# ONOFRE_WIRE_SHIELD.net
KiCad netlist of a schematic drawn in EAGLE
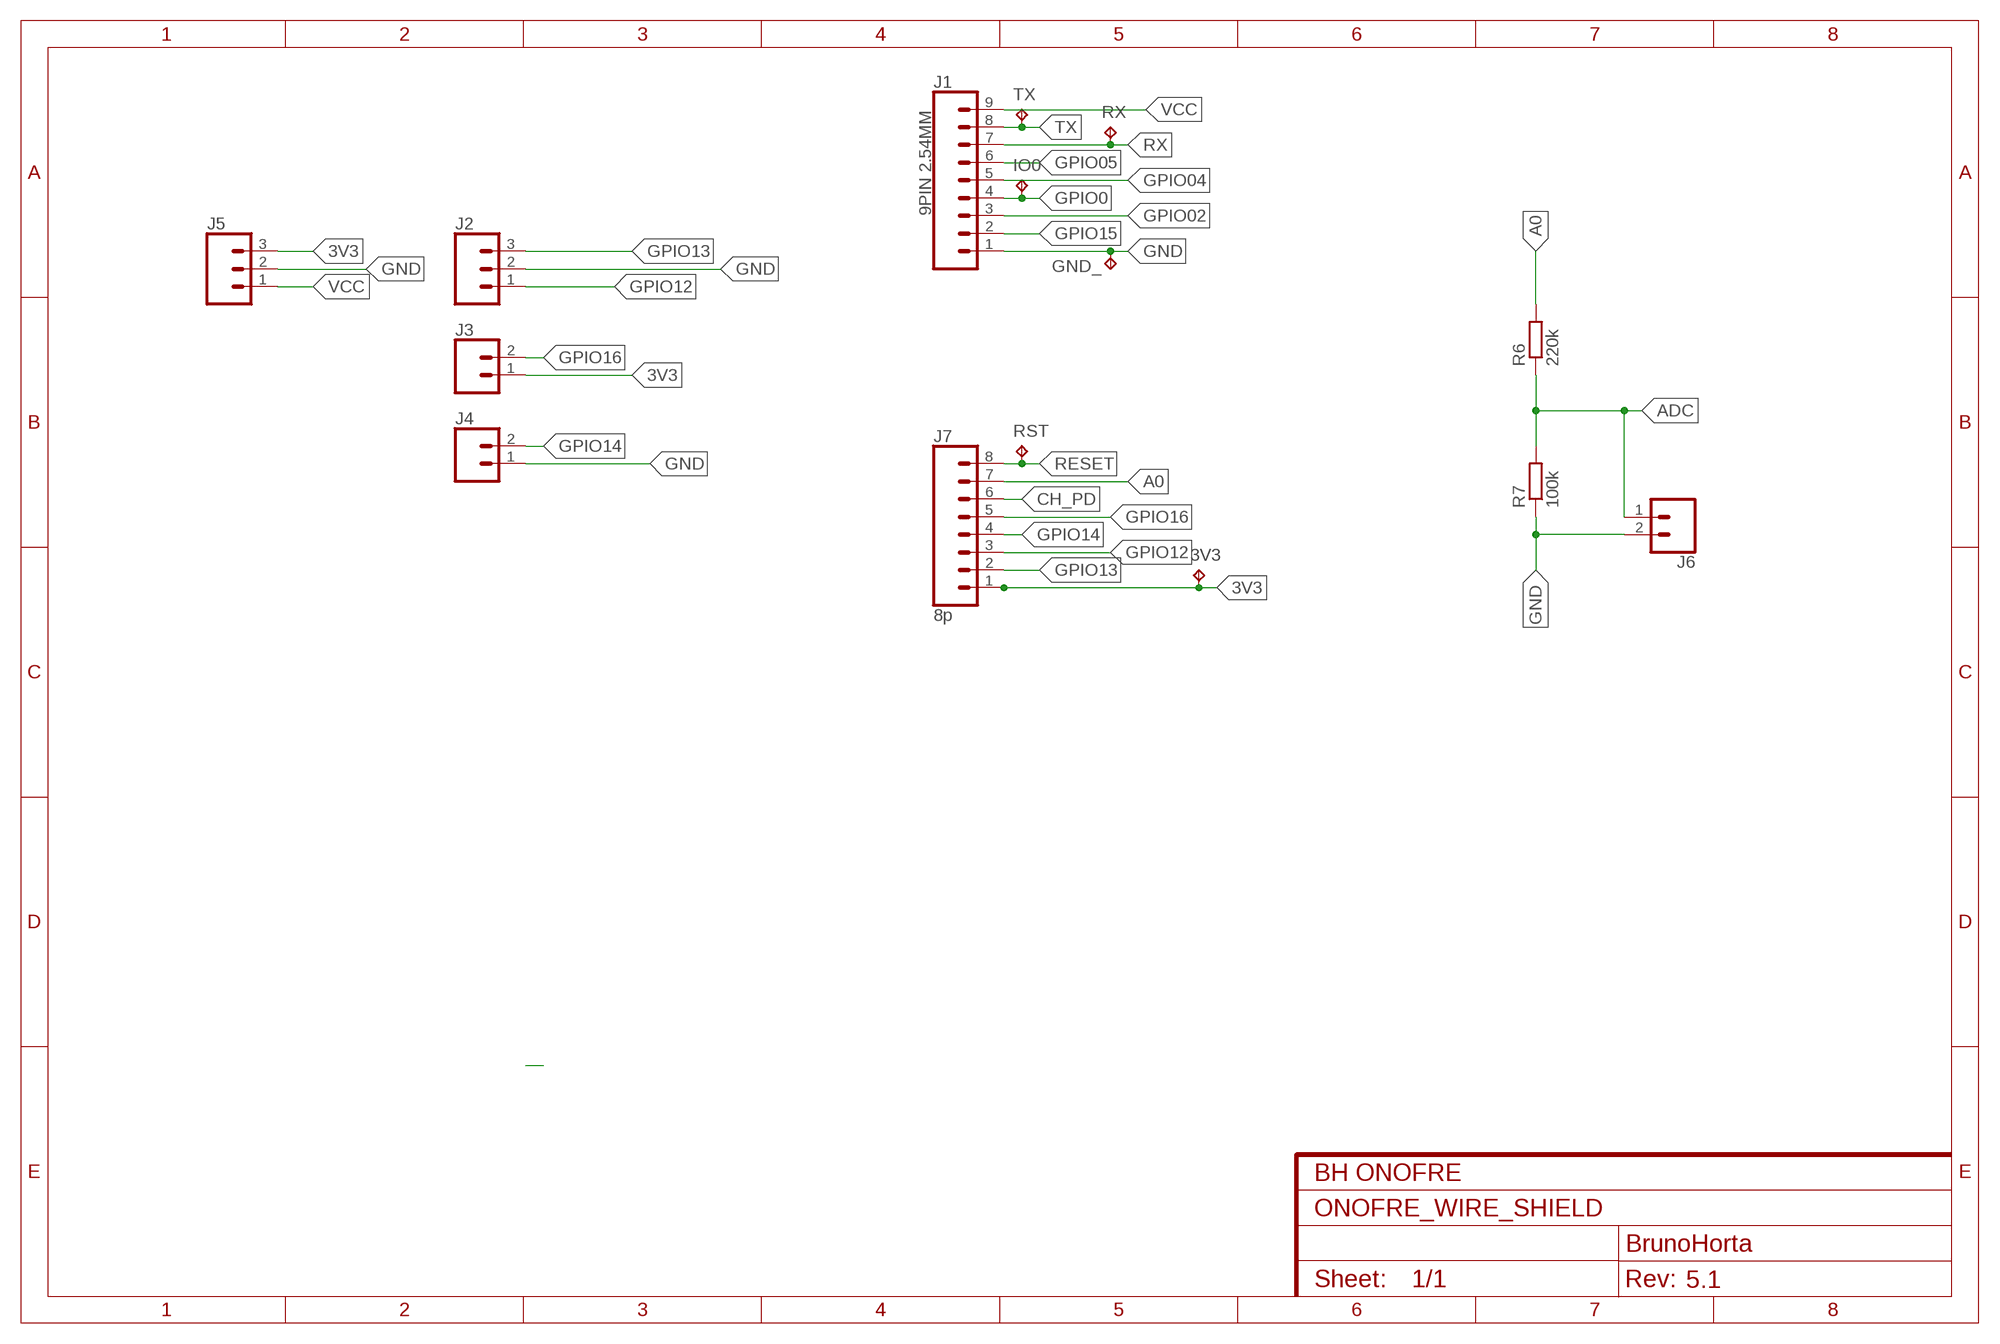
[diagram p0: schematic, sheet 1]

(export (version "E")
  (design (tool "Eeschema 10.0.6"))
  (components
    (comp (ref "3V3")
      (value "TPB1,27")
      (footprint "eagle-import:B1,27")
      (libsource (lib "eagle-import") (part "TPB1,27"))
    )
    (comp (ref "GND_")
      (value "TPB1,27")
      (footprint "eagle-import:B1,27")
      (libsource (lib "eagle-import") (part "TPB1,27"))
    )
    (comp (ref "IO0")
      (value "TPB1,27")
      (footprint "eagle-import:B1,27")
      (libsource (lib "eagle-import") (part "TPB1,27"))
    )
    (comp (ref "J1")
      (value "9PIN 2.54MM")
      (footprint "eagle-import:1X09")
      (libsource (lib "eagle-import") (part "CONN_09"))
    )
    (comp (ref "J2")
      (value "CONN_03")
      (footprint "eagle-import:1X03")
      (libsource (lib "eagle-import") (part "CONN_03"))
    )
    (comp (ref "J3")
      (value "CONN_02")
      (footprint "eagle-import:1X02")
      (libsource (lib "eagle-import") (part "CONN_02"))
    )
    (comp (ref "J4")
      (value "CONN_02")
      (footprint "eagle-import:1X02")
      (libsource (lib "eagle-import") (part "CONN_02"))
    )
    (comp (ref "J5")
      (value "CONN_03")
      (footprint "eagle-import:1X03")
      (libsource (lib "eagle-import") (part "CONN_03"))
    )
    (comp (ref "J6")
      (value "CONN_02")
      (footprint "eagle-import:1X02")
      (libsource (lib "eagle-import") (part "CONN_02"))
    )
    (comp (ref "J7")
      (value "8p")
      (footprint "eagle-import:1X08")
      (libsource (lib "eagle-import") (part "CONN_08{dblquote}"))
    )
    (comp (ref "R6")
      (value "220k")
      (footprint "eagle-import:R0603")
      (libsource (lib "eagle-import") (part "R-EU_R0603"))
    )
    (comp (ref "R7")
      (value "100k")
      (footprint "eagle-import:R0603")
      (libsource (lib "eagle-import") (part "R-EU_R0603"))
    )
    (comp (ref "RST")
      (value "TPB1,27")
      (footprint "eagle-import:B1,27")
      (libsource (lib "eagle-import") (part "TPB1,27"))
    )
    (comp (ref "RX")
      (value "TPB1,27")
      (footprint "eagle-import:B1,27")
      (libsource (lib "eagle-import") (part "TPB1,27"))
    )
    (comp (ref "TX")
      (value "TPB1,27")
      (footprint "eagle-import:B1,27")
      (libsource (lib "eagle-import") (part "TPB1,27"))
    )
  )
  (nets
    (net (code "1") (name "3V3") (class "Default")
      (node (ref "3V3") (pin "TP") (pinfunction "TP_TP") (pintype "input"))
      (node (ref "J3") (pin "1") (pinfunction "1_1") (pintype "passive"))
      (node (ref "J5") (pin "3") (pinfunction "3_3") (pintype "passive"))
      (node (ref "J7") (pin "1") (pinfunction "1_1") (pintype "passive"))
    )
    (net (code "2") (name "A0") (class "Default")
      (node (ref "J7") (pin "7") (pinfunction "7_7") (pintype "passive"))
      (node (ref "R6") (pin "2") (pinfunction "2_2") (pintype "passive"))
    )
    (net (code "3") (name "ADC") (class "Default")
      (node (ref "J6") (pin "1") (pinfunction "1_1") (pintype "passive"))
      (node (ref "R6") (pin "1") (pinfunction "1_1") (pintype "passive"))
      (node (ref "R7") (pin "2") (pinfunction "2_2") (pintype "passive"))
    )
    (net (code "4") (name "CH_PD") (class "Default")
      (node (ref "J7") (pin "6") (pinfunction "6_6") (pintype "passive"))
    )
    (net (code "5") (name "GND") (class "Default")
      (node (ref "GND_") (pin "TP") (pinfunction "TP_TP") (pintype "input"))
      (node (ref "J1") (pin "1") (pinfunction "1_1") (pintype "passive"))
      (node (ref "J2") (pin "2") (pinfunction "2_2") (pintype "passive"))
      (node (ref "J4") (pin "1") (pinfunction "1_1") (pintype "passive"))
      (node (ref "J5") (pin "2") (pinfunction "2_2") (pintype "passive"))
      (node (ref "J6") (pin "2") (pinfunction "2_2") (pintype "passive"))
      (node (ref "R7") (pin "1") (pinfunction "1_1") (pintype "passive"))
    )
    (net (code "6") (name "GPIO0") (class "Default")
      (node (ref "IO0") (pin "TP") (pinfunction "TP_TP") (pintype "input"))
      (node (ref "J1") (pin "4") (pinfunction "4_4") (pintype "passive"))
    )
    (net (code "7") (name "GPIO02") (class "Default")
      (node (ref "J1") (pin "3") (pinfunction "3_3") (pintype "passive"))
    )
    (net (code "8") (name "GPIO04") (class "Default")
      (node (ref "J1") (pin "5") (pinfunction "5_5") (pintype "passive"))
    )
    (net (code "9") (name "GPIO05") (class "Default")
      (node (ref "J1") (pin "6") (pinfunction "6_6") (pintype "passive"))
    )
    (net (code "10") (name "GPIO12") (class "Default")
      (node (ref "J2") (pin "1") (pinfunction "1_1") (pintype "passive"))
      (node (ref "J7") (pin "3") (pinfunction "3_3") (pintype "passive"))
    )
    (net (code "11") (name "GPIO13") (class "Default")
      (node (ref "J2") (pin "3") (pinfunction "3_3") (pintype "passive"))
      (node (ref "J7") (pin "2") (pinfunction "2_2") (pintype "passive"))
    )
    (net (code "12") (name "GPIO14") (class "Default")
      (node (ref "J4") (pin "2") (pinfunction "2_2") (pintype "passive"))
      (node (ref "J7") (pin "4") (pinfunction "4_4") (pintype "passive"))
    )
    (net (code "13") (name "GPIO15") (class "Default")
      (node (ref "J1") (pin "2") (pinfunction "2_2") (pintype "passive"))
    )
    (net (code "14") (name "GPIO16") (class "Default")
      (node (ref "J3") (pin "2") (pinfunction "2_2") (pintype "passive"))
      (node (ref "J7") (pin "5") (pinfunction "5_5") (pintype "passive"))
    )
    (net (code "15") (name "RESET") (class "Default")
      (node (ref "J7") (pin "8") (pinfunction "8_8") (pintype "passive"))
      (node (ref "RST") (pin "TP") (pinfunction "TP_TP") (pintype "input"))
    )
    (net (code "16") (name "RX") (class "Default")
      (node (ref "J1") (pin "7") (pinfunction "7_7") (pintype "passive"))
      (node (ref "RX") (pin "TP") (pinfunction "TP_TP") (pintype "input"))
    )
    (net (code "17") (name "TX") (class "Default")
      (node (ref "J1") (pin "8") (pinfunction "8_8") (pintype "passive"))
      (node (ref "TX") (pin "TP") (pinfunction "TP_TP") (pintype "input"))
    )
    (net (code "18") (name "VCC") (class "Default")
      (node (ref "J1") (pin "9") (pinfunction "9_9") (pintype "passive"))
      (node (ref "J5") (pin "1") (pinfunction "1_1") (pintype "passive"))
    )
  )
)
